# 4_-_DDR2_DRAM.net
KiCad netlist of a schematic drawn in Altium Designer
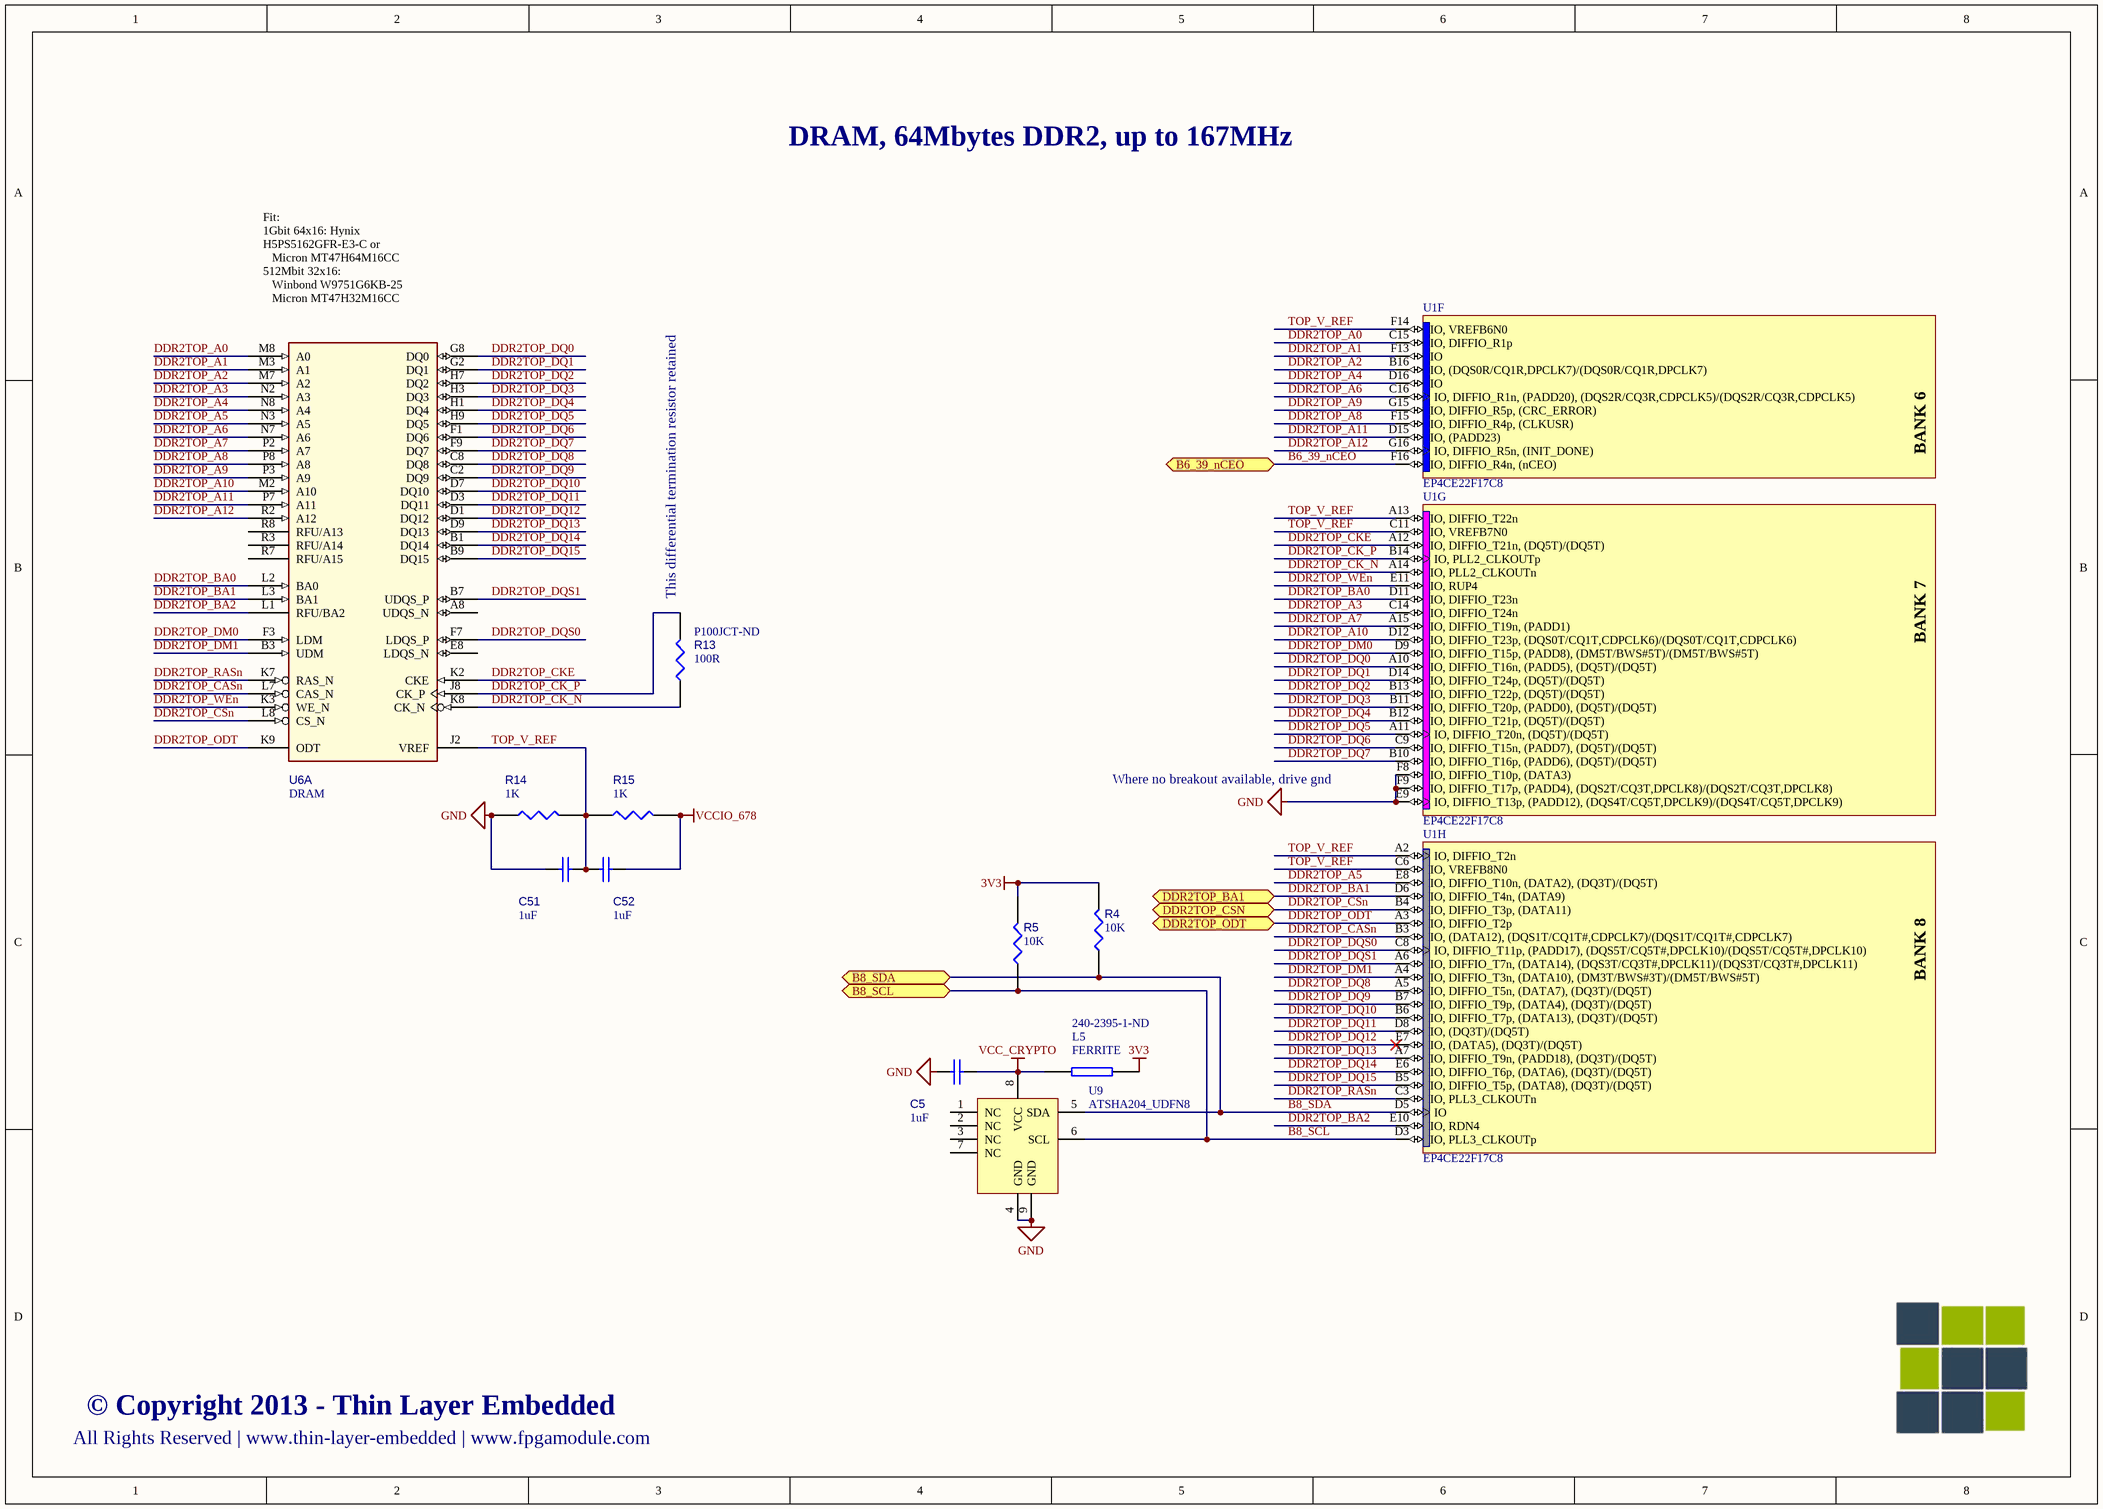
[diagram p0: 4 - DDR2 DRAM.SchDoc]

(export (version "E")
  (design (tool "Eeschema 10.0.6"))
  (components
    (comp (ref "C5")
      (value "1uF")
      (footprint "0402_HD")
      (description "Capacitor")
      (libsource (lib "*") (part "CAP"))
    )
    (comp (ref "C51")
      (value "1uF")
      (footprint "0402_HD")
      (description "Capacitor")
      (libsource (lib "*") (part "CAP"))
    )
    (comp (ref "C52")
      (value "1uF")
      (footprint "0402_HD")
      (description "Capacitor")
      (libsource (lib "*") (part "CAP"))
    )
    (comp (ref "L5")
      (value "FERRITE")
      (footprint "0402_HD")
      (description "FERRITE CHIP POWER 80 OHM SMD")
      (fields
        (field (name "SUPPLIER PART NUMBER 1") "240-2395-1-ND")
        (field (name "MANUFACTURER") "Laird-Signal Integrity Products")
        (field (name "MANUFACTURER PART NUMBER") "HI0805R800R-10")
      )
      (libsource (lib "tea133-SCH-1") (part "FERRITE"))
    )
    (comp (ref "R4") (value "10K") (footprint "0402_HD") (libsource (lib "*") (part "RES1")))
    (comp (ref "R5") (value "10K") (footprint "0402_HD") (libsource (lib "*") (part "RES1")))
    (comp (ref "R13")
      (value "100R")
      (footprint "0402_HD")
      (description "RES 100 OHM 1/10W 5% 0402 SMD")
      (fields
        (field (name "SUPPLIER PART NUMBER 1") "P100JCT-ND")
        (field (name "MANUFACTURER") "Panasonic - ECG")
        (field (name "MANUFACTURER PART NUMBER") "ERJ-2GEJ101X")
      )
      (libsource (lib "") (part "RES1_1"))
    )
    (comp (ref "R14")
      (value "1K")
      (footprint "0402_HD")
      (description "RES 1.0K OHM 1/10W 5% 0603 SMD")
      (fields
        (field (name "MANUFACTURER") "Yageo")
        (field (name "MANUFACTURER PART NUMBER") "RC0603JR-071KL")
      )
      (libsource (lib "*") (part "RES1"))
    )
    (comp (ref "R15")
      (value "1K")
      (footprint "0402_HD")
      (description "RES 1.0K OHM 1/10W 5% 0603 SMD")
      (fields
        (field (name "MANUFACTURER") "Yageo")
        (field (name "MANUFACTURER PART NUMBER") "RC0603JR-071KL")
      )
      (libsource (lib "*") (part "RES1"))
    )
    (comp (ref "U1")
      (value "EP4CE22F17C8")
      (footprint "FBGA256")
      (fields (field (name "PUBLISHER") "Altium Limited"))
      (libsource (lib "OB_EP4CE15E22") (part "EP4CE22F17C8"))
    )
    (comp (ref "U6")
      (value "DRAM")
      (footprint "DDR2_84_SPEC_HD")
      (description "IC DDR2 SDRAM 32M X 16 4 BANKS 333MHZ CAS LATENCY 5 FBGA PACKAGE 84 PINS 1.8V CORE 1.8V IO")
      (libsource (lib "OB_EP4CE15E22") (part "MT47H32M16CC"))
    )
    (comp (ref "U9")
      (value "ATSHA204_UDFN8")
      (footprint "UDFN8")
      (libsource (lib "SHERPA_1A") (part "ATSHA204_UDFN8"))
    )
  )
  (nets
    (net (code "1") (name "/B6_39_nCEO") (class "Default")
      (node (ref "U1") (pin "F16") (pinfunction "IO,_DIFFIO_R4n,_(nCEO)_F16") (pintype "bidirectional"))
    )
    (net (code "2") (name "/B8_SCL") (class "Default")
      (node (ref "R5") (pin "2") (pinfunction "2_2") (pintype "passive"))
      (node (ref "U1") (pin "D3") (pinfunction "IO,_PLL3_CLKOUTp_D3") (pintype "bidirectional"))
      (node (ref "U9") (pin "6") (pinfunction "SCL_6") (pintype "passive"))
    )
    (net (code "3") (name "/B8_SDA") (class "Default")
      (node (ref "R4") (pin "2") (pinfunction "2_2") (pintype "passive"))
      (node (ref "U1") (pin "D5") (pinfunction "IO_D5") (pintype "bidirectional"))
      (node (ref "U9") (pin "5") (pinfunction "SDA_5") (pintype "passive"))
    )
    (net (code "4") (name "/DDR2TOP_A0") (class "Default")
      (node (ref "U1") (pin "C15") (pinfunction "IO,_DIFFIO_R1p_C15") (pintype "bidirectional"))
      (node (ref "U6") (pin "M8") (pinfunction "A0_M8") (pintype "input"))
    )
    (net (code "5") (name "/DDR2TOP_A1") (class "Default")
      (node (ref "U1") (pin "F13") (pinfunction "IO_F13") (pintype "bidirectional"))
      (node (ref "U6") (pin "M3") (pinfunction "A1_M3") (pintype "input"))
    )
    (net (code "6") (name "/DDR2TOP_A2") (class "Default")
      (node (ref "U1") (pin "B16") (pinfunction "IO,_(DQS0R/CQ1R,DPCLK7)/(DQS0R/CQ1R,DPCLK7)_B16") (pintype "bidirectional"))
      (node (ref "U6") (pin "M7") (pinfunction "A2_M7") (pintype "input"))
    )
    (net (code "7") (name "/DDR2TOP_A3") (class "Default")
      (node (ref "U1") (pin "C14") (pinfunction "IO,_DIFFIO_T24n_C14") (pintype "bidirectional"))
      (node (ref "U6") (pin "N2") (pinfunction "A3_N2") (pintype "input"))
    )
    (net (code "8") (name "/DDR2TOP_A4") (class "Default")
      (node (ref "U1") (pin "D16") (pinfunction "IO_D16") (pintype "bidirectional"))
      (node (ref "U6") (pin "N8") (pinfunction "A4_N8") (pintype "input"))
    )
    (net (code "9") (name "/DDR2TOP_A5") (class "Default")
      (node (ref "U1") (pin "E8") (pinfunction "IO,_DIFFIO_T10n,_(DATA2),_(DQ3T)/(DQ5T)_E8") (pintype "bidirectional"))
      (node (ref "U6") (pin "N3") (pinfunction "A5_N3") (pintype "input"))
    )
    (net (code "10") (name "/DDR2TOP_A6") (class "Default")
      (node (ref "U1") (pin "C16") (pinfunction "IO,_DIFFIO_R1n,_(PADD20),_(DQS2R/CQ3R,CDPCLK5)/(DQS2R/CQ3R,CDPCLK5)_C16") (pintype "bidirectional"))
      (node (ref "U6") (pin "N7") (pinfunction "A6_N7") (pintype "input"))
    )
    (net (code "11") (name "/DDR2TOP_A7") (class "Default")
      (node (ref "U1") (pin "A15") (pinfunction "IO,_DIFFIO_T19n,_(PADD1)_A15") (pintype "bidirectional"))
      (node (ref "U6") (pin "P2") (pinfunction "A7_P2") (pintype "input"))
    )
    (net (code "12") (name "/DDR2TOP_A8") (class "Default")
      (node (ref "U1") (pin "F15") (pinfunction "IO,_DIFFIO_R4p,_(CLKUSR)_F15") (pintype "bidirectional"))
      (node (ref "U6") (pin "P8") (pinfunction "A8_P8") (pintype "input"))
    )
    (net (code "13") (name "/DDR2TOP_A9") (class "Default")
      (node (ref "U1") (pin "G15") (pinfunction "IO,_DIFFIO_R5p,_(CRC_ERROR)_G15") (pintype "bidirectional"))
      (node (ref "U6") (pin "P3") (pinfunction "A9_P3") (pintype "input"))
    )
    (net (code "14") (name "/DDR2TOP_A10") (class "Default")
      (node (ref "U1") (pin "D12") (pinfunction "IO,_DIFFIO_T23p,_(DQS0T/CQ1T,CDPCLK6)/(DQS0T/CQ1T,CDPCLK6)_D12") (pintype "bidirectional"))
      (node (ref "U6") (pin "M2") (pinfunction "A10_M2") (pintype "input"))
    )
    (net (code "15") (name "/DDR2TOP_A11") (class "Default")
      (node (ref "U1") (pin "D15") (pinfunction "IO,_(PADD23)_D15") (pintype "bidirectional"))
      (node (ref "U6") (pin "P7") (pinfunction "A11_P7") (pintype "input"))
    )
    (net (code "16") (name "/DDR2TOP_A12") (class "Default")
      (node (ref "U1") (pin "G16") (pinfunction "IO,_DIFFIO_R5n,_(INIT_DONE)_G16") (pintype "bidirectional"))
      (node (ref "U6") (pin "R2") (pinfunction "A12_R2") (pintype "input"))
    )
    (net (code "17") (name "/DDR2TOP_BA0") (class "Default")
      (node (ref "U1") (pin "D11") (pinfunction "IO,_DIFFIO_T23n_D11") (pintype "bidirectional"))
      (node (ref "U6") (pin "L2") (pinfunction "BA0_L2") (pintype "input"))
    )
    (net (code "18") (name "/DDR2TOP_BA1") (class "Default")
      (node (ref "U1") (pin "D6") (pinfunction "IO,_DIFFIO_T4n,_(DATA9)_D6") (pintype "bidirectional"))
      (node (ref "U6") (pin "L3") (pinfunction "BA1_L3") (pintype "input"))
    )
    (net (code "19") (name "/DDR2TOP_BA2") (class "Default")
      (node (ref "U1") (pin "E10") (pinfunction "IO,_RDN4_E10") (pintype "bidirectional"))
      (node (ref "U6") (pin "L1") (pinfunction "RFU/BA2_L1") (pintype "passive"))
    )
    (net (code "20") (name "/DDR2TOP_CASn") (class "Default")
      (node (ref "U1") (pin "B3") (pinfunction "IO,_(DATA12),_(DQS1T/CQ1T#,CDPCLK7)/(DQS1T/CQ1T#,CDPCLK7)_B3") (pintype "bidirectional"))
      (node (ref "U6") (pin "L7") (pinfunction "CAS_N_L7") (pintype "input"))
    )
    (net (code "21") (name "/DDR2TOP_CKE") (class "Default")
      (node (ref "U1") (pin "A12") (pinfunction "IO,_DIFFIO_T21n,_(DQ5T)/(DQ5T)_A12") (pintype "bidirectional"))
      (node (ref "U6") (pin "K2") (pinfunction "CKE_K2") (pintype "input"))
    )
    (net (code "22") (name "/DDR2TOP_CK_N") (class "Default")
      (node (ref "R13") (pin "2") (pinfunction "2_2") (pintype "passive"))
      (node (ref "U1") (pin "A14") (pinfunction "IO,_PLL2_CLKOUTn_A14") (pintype "bidirectional"))
      (node (ref "U6") (pin "K8") (pinfunction "CK_N_K8") (pintype "input"))
    )
    (net (code "23") (name "/DDR2TOP_CK_P") (class "Default")
      (node (ref "R13") (pin "1") (pinfunction "1_1") (pintype "passive"))
      (node (ref "U1") (pin "B14") (pinfunction "IO,_PLL2_CLKOUTp_B14") (pintype "bidirectional"))
      (node (ref "U6") (pin "J8") (pinfunction "CK_P_J8") (pintype "input"))
    )
    (net (code "24") (name "/DDR2TOP_CSn") (class "Default")
      (node (ref "U1") (pin "B4") (pinfunction "IO,_DIFFIO_T3p,_(DATA11)_B4") (pintype "bidirectional"))
      (node (ref "U6") (pin "L8") (pinfunction "CS_N_L8") (pintype "input"))
    )
    (net (code "25") (name "/DDR2TOP_DM0") (class "Default")
      (node (ref "U1") (pin "D9") (pinfunction "IO,_DIFFIO_T15p,_(PADD8),_(DM5T/BWS#5T)/(DM5T/BWS#5T)_D9") (pintype "bidirectional"))
      (node (ref "U6") (pin "F3") (pinfunction "LDM_F3") (pintype "input"))
    )
    (net (code "26") (name "/DDR2TOP_DM1") (class "Default")
      (node (ref "U1") (pin "A4") (pinfunction "IO,_DIFFIO_T3n,_(DATA10),_(DM3T/BWS#3T)/(DM5T/BWS#5T)_A4") (pintype "bidirectional"))
      (node (ref "U6") (pin "B3") (pinfunction "UDM_B3") (pintype "input"))
    )
    (net (code "27") (name "/DDR2TOP_DQ0") (class "Default")
      (node (ref "U1") (pin "A10") (pinfunction "IO,_DIFFIO_T16n,_(PADD5),_(DQ5T)/(DQ5T)_A10") (pintype "bidirectional"))
      (node (ref "U6") (pin "G8") (pinfunction "DQ0_G8") (pintype "bidirectional"))
    )
    (net (code "28") (name "/DDR2TOP_DQ1") (class "Default")
      (node (ref "U1") (pin "D14") (pinfunction "IO,_DIFFIO_T24p,_(DQ5T)/(DQ5T)_D14") (pintype "bidirectional"))
      (node (ref "U6") (pin "G2") (pinfunction "DQ1_G2") (pintype "bidirectional"))
    )
    (net (code "29") (name "/DDR2TOP_DQ2") (class "Default")
      (node (ref "U1") (pin "B13") (pinfunction "IO,_DIFFIO_T22p,_(DQ5T)/(DQ5T)_B13") (pintype "bidirectional"))
      (node (ref "U6") (pin "H7") (pinfunction "DQ2_H7") (pintype "bidirectional"))
    )
    (net (code "30") (name "/DDR2TOP_DQ3") (class "Default")
      (node (ref "U1") (pin "B11") (pinfunction "IO,_DIFFIO_T20p,_(PADD0),_(DQ5T)/(DQ5T)_B11") (pintype "bidirectional"))
      (node (ref "U6") (pin "H3") (pinfunction "DQ3_H3") (pintype "bidirectional"))
    )
    (net (code "31") (name "/DDR2TOP_DQ4") (class "Default")
      (node (ref "U1") (pin "B12") (pinfunction "IO,_DIFFIO_T21p,_(DQ5T)/(DQ5T)_B12") (pintype "bidirectional"))
      (node (ref "U6") (pin "H1") (pinfunction "DQ4_H1") (pintype "bidirectional"))
    )
    (net (code "32") (name "/DDR2TOP_DQ5") (class "Default")
      (node (ref "U1") (pin "A11") (pinfunction "IO,_DIFFIO_T20n,_(DQ5T)/(DQ5T)_A11") (pintype "bidirectional"))
      (node (ref "U6") (pin "H9") (pinfunction "DQ5_H9") (pintype "bidirectional"))
    )
    (net (code "33") (name "/DDR2TOP_DQ6") (class "Default")
      (node (ref "U1") (pin "C9") (pinfunction "IO,_DIFFIO_T15n,_(PADD7),_(DQ5T)/(DQ5T)_C9") (pintype "bidirectional"))
      (node (ref "U6") (pin "F1") (pinfunction "DQ6_F1") (pintype "bidirectional"))
    )
    (net (code "34") (name "/DDR2TOP_DQ7") (class "Default")
      (node (ref "U1") (pin "B10") (pinfunction "IO,_DIFFIO_T16p,_(PADD6),_(DQ5T)/(DQ5T)_B10") (pintype "bidirectional"))
      (node (ref "U6") (pin "F9") (pinfunction "DQ7_F9") (pintype "bidirectional"))
    )
    (net (code "35") (name "/DDR2TOP_DQ8") (class "Default")
      (node (ref "U1") (pin "A5") (pinfunction "IO,_DIFFIO_T5n,_(DATA7),_(DQ3T)/(DQ5T)_A5") (pintype "bidirectional"))
      (node (ref "U6") (pin "C8") (pinfunction "DQ8_C8") (pintype "bidirectional"))
    )
    (net (code "36") (name "/DDR2TOP_DQ9") (class "Default")
      (node (ref "U1") (pin "B7") (pinfunction "IO,_DIFFIO_T9p,_(DATA4),_(DQ3T)/(DQ5T)_B7") (pintype "bidirectional"))
      (node (ref "U6") (pin "C2") (pinfunction "DQ9_C2") (pintype "bidirectional"))
    )
    (net (code "37") (name "/DDR2TOP_DQ10") (class "Default")
      (node (ref "U1") (pin "B6") (pinfunction "IO,_DIFFIO_T7p,_(DATA13),_(DQ3T)/(DQ5T)_B6") (pintype "bidirectional"))
      (node (ref "U6") (pin "D7") (pinfunction "DQ10_D7") (pintype "bidirectional"))
    )
    (net (code "38") (name "/DDR2TOP_DQ11") (class "Default")
      (node (ref "U1") (pin "D8") (pinfunction "IO,_(DQ3T)/(DQ5T)_D8") (pintype "bidirectional"))
      (node (ref "U6") (pin "D3") (pinfunction "DQ11_D3") (pintype "bidirectional"))
    )
    (net (code "39") (name "/DDR2TOP_DQ12") (class "Default")
      (node (ref "U1") (pin "E7") (pinfunction "IO,_(DATA5),_(DQ3T)/(DQ5T)_E7") (pintype "bidirectional"))
      (node (ref "U6") (pin "D1") (pinfunction "DQ12_D1") (pintype "bidirectional"))
    )
    (net (code "40") (name "/DDR2TOP_DQ13") (class "Default")
      (node (ref "U1") (pin "A7") (pinfunction "IO,_DIFFIO_T9n,_(PADD18),_(DQ3T)/(DQ5T)_A7") (pintype "bidirectional"))
      (node (ref "U6") (pin "D9") (pinfunction "DQ13_D9") (pintype "bidirectional"))
    )
    (net (code "41") (name "/DDR2TOP_DQ14") (class "Default")
      (node (ref "U1") (pin "E6") (pinfunction "IO,_DIFFIO_T6p,_(DATA6),_(DQ3T)/(DQ5T)_E6") (pintype "bidirectional"))
      (node (ref "U6") (pin "B1") (pinfunction "DQ14_B1") (pintype "bidirectional"))
    )
    (net (code "42") (name "/DDR2TOP_DQ15") (class "Default")
      (node (ref "U1") (pin "B5") (pinfunction "IO,_DIFFIO_T5p,_(DATA8),_(DQ3T)/(DQ5T)_B5") (pintype "bidirectional"))
      (node (ref "U6") (pin "B9") (pinfunction "DQ15_B9") (pintype "bidirectional"))
    )
    (net (code "43") (name "/DDR2TOP_DQS0") (class "Default")
      (node (ref "U1") (pin "C8") (pinfunction "IO,_DIFFIO_T11p,_(PADD17),_(DQS5T/CQ5T#,DPCLK10)/(DQS5T/CQ5T#,DPCLK10)_C8") (pintype "bidirectional"))
      (node (ref "U6") (pin "F7") (pinfunction "LDQS_P_F7") (pintype "bidirectional"))
    )
    (net (code "44") (name "/DDR2TOP_DQS1") (class "Default")
      (node (ref "U1") (pin "A6") (pinfunction "IO,_DIFFIO_T7n,_(DATA14),_(DQS3T/CQ3T#,DPCLK11)/(DQS3T/CQ3T#,DPCLK11)_A6") (pintype "bidirectional"))
      (node (ref "U6") (pin "B7") (pinfunction "UDQS_P_B7") (pintype "bidirectional"))
    )
    (net (code "45") (name "/DDR2TOP_ODT") (class "Default")
      (node (ref "U1") (pin "A3") (pinfunction "IO,_DIFFIO_T2p_A3") (pintype "bidirectional"))
      (node (ref "U6") (pin "K9") (pinfunction "ODT_K9") (pintype "passive"))
    )
    (net (code "46") (name "/DDR2TOP_RASn") (class "Default")
      (node (ref "U1") (pin "C3") (pinfunction "IO,_PLL3_CLKOUTn_C3") (pintype "bidirectional"))
      (node (ref "U6") (pin "K7") (pinfunction "RAS_N_K7") (pintype "input"))
    )
    (net (code "47") (name "/DDR2TOP_WEn") (class "Default")
      (node (ref "U1") (pin "E11") (pinfunction "IO,_RUP4_E11") (pintype "bidirectional"))
      (node (ref "U6") (pin "K3") (pinfunction "WE_N_K3") (pintype "input"))
    )
    (net (code "48") (name "/TOP_V_REF") (class "Default")
      (node (ref "C51") (pin "1") (pinfunction "1_1") (pintype "passive"))
      (node (ref "C52") (pin "2") (pinfunction "2_2") (pintype "passive"))
      (node (ref "R14") (pin "1") (pinfunction "1_1") (pintype "passive"))
      (node (ref "R15") (pin "2") (pinfunction "2_2") (pintype "passive"))
      (node (ref "U1") (pin "A13") (pinfunction "IO,_DIFFIO_T22n_A13") (pintype "bidirectional"))
      (node (ref "U1") (pin "A2") (pinfunction "IO,_DIFFIO_T2n_A2") (pintype "bidirectional"))
      (node (ref "U1") (pin "C11") (pinfunction "IO,_VREFB7N0_C11") (pintype "bidirectional"))
      (node (ref "U1") (pin "C6") (pinfunction "IO,_VREFB8N0_C6") (pintype "bidirectional"))
      (node (ref "U1") (pin "F14") (pinfunction "IO,_VREFB6N0_F14") (pintype "bidirectional"))
      (node (ref "U6") (pin "J2") (pinfunction "VREF_J2") (pintype "power_in"))
    )
    (net (code "49") (name "3V3") (class "Default")
      (node (ref "L5") (pin "2") (pinfunction "2_2") (pintype "passive"))
      (node (ref "R4") (pin "1") (pinfunction "1_1") (pintype "passive"))
      (node (ref "R5") (pin "1") (pinfunction "1_1") (pintype "passive"))
    )
    (net (code "50") (name "GND") (class "Default")
      (node (ref "C5") (pin "2") (pinfunction "2_2") (pintype "passive"))
      (node (ref "C51") (pin "2") (pinfunction "2_2") (pintype "passive"))
      (node (ref "R14") (pin "2") (pinfunction "2_2") (pintype "passive"))
      (node (ref "U1") (pin "E9") (pinfunction "IO,_DIFFIO_T13p,_(PADD12),_(DQS4T/CQ5T,DPCLK9)/(DQS4T/CQ5T,DPCLK9)_E9") (pintype "bidirectional"))
      (node (ref "U1") (pin "F8") (pinfunction "IO,_DIFFIO_T10p,_(DATA3)_F8") (pintype "bidirectional"))
      (node (ref "U1") (pin "F9") (pinfunction "IO,_DIFFIO_T17p,_(PADD4),_(DQS2T/CQ3T,DPCLK8)/(DQS2T/CQ3T,DPCLK8)_F9") (pintype "bidirectional"))
      (node (ref "U9") (pin "4") (pinfunction "GND_4") (pintype "passive"))
      (node (ref "U9") (pin "9") (pinfunction "GND_9") (pintype "passive"))
    )
    (net (code "51") (name "VCCIO_678") (class "Default")
      (node (ref "C52") (pin "1") (pinfunction "1_1") (pintype "passive"))
      (node (ref "R15") (pin "1") (pinfunction "1_1") (pintype "passive"))
    )
    (net (code "52") (name "VCC_CRYPTO") (class "Default")
      (node (ref "C5") (pin "1") (pinfunction "1_1") (pintype "passive"))
      (node (ref "L5") (pin "1") (pinfunction "1_1") (pintype "passive"))
      (node (ref "U9") (pin "8") (pinfunction "VCC_8") (pintype "passive"))
    )
    (net (code "53") (name "unconnected-(U6A-LDQS_N-PadE8)") (class "Default")
      (node (ref "U6") (pin "E8") (pinfunction "LDQS_N_E8") (pintype "bidirectional"))
    )
    (net (code "54") (name "unconnected-(U6A-RFU{slash}A13-PadR8)") (class "Default")
      (node (ref "U6") (pin "R8") (pinfunction "RFU/A13_R8") (pintype "passive"))
    )
    (net (code "55") (name "unconnected-(U6A-RFU{slash}A14-PadR3)") (class "Default")
      (node (ref "U6") (pin "R3") (pinfunction "RFU/A14_R3") (pintype "passive"))
    )
    (net (code "56") (name "unconnected-(U6A-RFU{slash}A15-PadR7)") (class "Default")
      (node (ref "U6") (pin "R7") (pinfunction "RFU/A15_R7") (pintype "passive"))
    )
    (net (code "57") (name "unconnected-(U6A-UDQS_N-PadA8)") (class "Default")
      (node (ref "U6") (pin "A8") (pinfunction "UDQS_N_A8") (pintype "bidirectional"))
    )
    (net (code "58") (name "unconnected-(U9-NC-Pad1)") (class "Default")
      (node (ref "U9") (pin "1") (pinfunction "NC_1") (pintype "passive"))
    )
    (net (code "59") (name "unconnected-(U9-NC-Pad2)") (class "Default")
      (node (ref "U9") (pin "2") (pinfunction "NC_2") (pintype "passive"))
    )
    (net (code "60") (name "unconnected-(U9-NC-Pad3)") (class "Default")
      (node (ref "U9") (pin "3") (pinfunction "NC_3") (pintype "passive"))
    )
    (net (code "61") (name "unconnected-(U9-NC-Pad7)") (class "Default")
      (node (ref "U9") (pin "7") (pinfunction "NC_7") (pintype "passive"))
    )
  )
)
